# meltdown_interface.net
KiCad netlist of a schematic drawn in Altium Designer
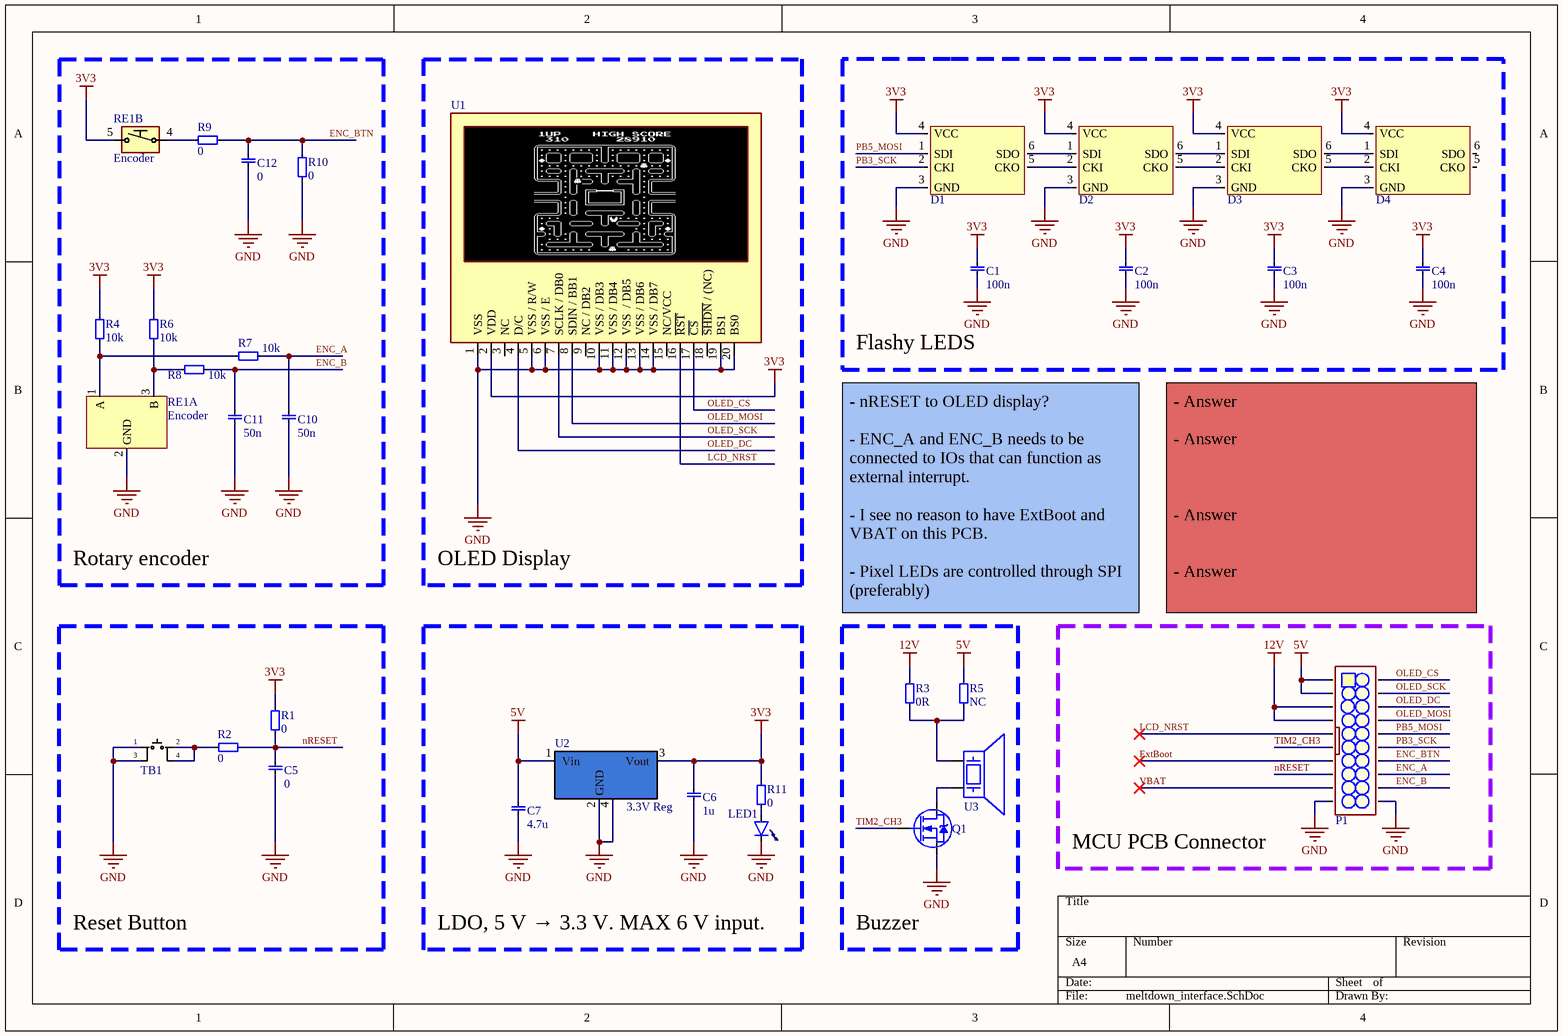
[diagram p0: meltdown_interface.SchDoc]

(export (version "E")
  (design (tool "Eeschema 10.0.6"))
  (components
    (comp (ref "C1")
      (value "100n")
      (footprint "0603 cap")
      (fields (field (name "Comment") "0603, capacitor"))
      (libsource (lib "jclib") (part "0603, capacitor"))
    )
    (comp (ref "C2")
      (value "100n")
      (footprint "0603 cap")
      (fields (field (name "Comment") "0603, capacitor"))
      (libsource (lib "jclib") (part "0603, capacitor"))
    )
    (comp (ref "C3")
      (value "100n")
      (footprint "0603 cap")
      (fields (field (name "Comment") "0603, capacitor"))
      (libsource (lib "jclib") (part "0603, capacitor"))
    )
    (comp (ref "C4")
      (value "100n")
      (footprint "0603 cap")
      (fields (field (name "Comment") "0603, capacitor"))
      (libsource (lib "jclib") (part "0603, capacitor"))
    )
    (comp (ref "C5")
      (value "0")
      (footprint "0603 cap")
      (fields (field (name "Comment") "0603, capacitor"))
      (libsource (lib "jclib") (part "0603, capacitor"))
    )
    (comp (ref "C6")
      (value "1u")
      (footprint "0603 cap")
      (fields (field (name "Comment") "0603, capacitor"))
      (libsource (lib "jclib") (part "0603, capacitor"))
    )
    (comp (ref "C7")
      (value "4.7u")
      (footprint "0603 cap")
      (fields (field (name "Comment") "0603, capacitor"))
      (libsource (lib "jclib") (part "0603, capacitor"))
    )
    (comp (ref "C10")
      (value "50n")
      (footprint "0603 cap")
      (fields (field (name "Comment") "0603, capacitor"))
      (libsource (lib "jclib") (part "0603, capacitor"))
    )
    (comp (ref "C11")
      (value "50n")
      (footprint "0603 cap")
      (fields (field (name "Comment") "0603, capacitor"))
      (libsource (lib "jclib") (part "0603, capacitor"))
    )
    (comp (ref "C12")
      (value "0")
      (footprint "0603 cap")
      (fields (field (name "Comment") "0603, capacitor"))
      (libsource (lib "jclib") (part "0603, capacitor"))
    )
    (comp (ref "D1")
      (value "Neo - SK9822")
      (footprint "SK9822")
      (libsource (lib "jclib") (part "Neo - SK9822"))
    )
    (comp (ref "D2")
      (value "Neo - SK9822")
      (footprint "SK9822")
      (libsource (lib "jclib") (part "Neo - SK9822"))
    )
    (comp (ref "D3")
      (value "Neo - SK9822")
      (footprint "SK9822")
      (libsource (lib "jclib") (part "Neo - SK9822"))
    )
    (comp (ref "D4")
      (value "Neo - SK9822")
      (footprint "SK9822")
      (libsource (lib "jclib") (part "Neo - SK9822"))
    )
    (comp (ref "LED1")
      (value "0805, LED")
      (footprint "0805_led")
      (libsource (lib "jclib") (part "0805, LED"))
    )
    (comp (ref "P1")
      (value "2x10 Ribbon Header")
      (footprint "2x10_RIBBON_CABLE_CON")
      (description "2.54 mm")
      (libsource (lib "jclib") (part "2x10 Ribbon Header"))
    )
    (comp (ref "Q1")
      (value "BSS138")
      (footprint "SOT323")
      (description "N-Channel Logic Level Enhancement Mode Field Effect Transistor")
      (libsource (lib "jclib") (part "BSS138"))
    )
    (comp (ref "R1")
      (value "0")
      (footprint "0603")
      (fields (field (name "Comment") "0603, resistor"))
      (libsource (lib "jclib") (part "0603, resistor"))
    )
    (comp (ref "R2")
      (value "0")
      (footprint "0603")
      (fields (field (name "Comment") "0603, resistor"))
      (libsource (lib "jclib") (part "0603, resistor"))
    )
    (comp (ref "R3")
      (value "0R")
      (footprint "0603")
      (fields (field (name "Comment") "0603, resistor"))
      (libsource (lib "jclib") (part "0603, resistor"))
    )
    (comp (ref "R4")
      (value "10k")
      (footprint "0603")
      (fields (field (name "Comment") "0603, resistor"))
      (libsource (lib "jclib") (part "0603, resistor"))
    )
    (comp (ref "R5")
      (value "NC")
      (footprint "0603")
      (fields (field (name "Comment") "0603, resistor"))
      (libsource (lib "jclib") (part "0603, resistor"))
    )
    (comp (ref "R6")
      (value "10k")
      (footprint "0603")
      (fields (field (name "Comment") "0603, resistor"))
      (libsource (lib "jclib") (part "0603, resistor"))
    )
    (comp (ref "R7")
      (value "10k")
      (footprint "0603")
      (fields (field (name "Comment") "0603, resistor"))
      (libsource (lib "jclib") (part "0603, resistor"))
    )
    (comp (ref "R8")
      (value "10k")
      (footprint "0603")
      (fields (field (name "Comment") "0603, resistor"))
      (libsource (lib "jclib") (part "0603, resistor"))
    )
    (comp (ref "R9")
      (value "0")
      (footprint "0603")
      (fields (field (name "Comment") "0603, resistor"))
      (libsource (lib "jclib") (part "0603, resistor"))
    )
    (comp (ref "R10")
      (value "0")
      (footprint "0603")
      (fields (field (name "Comment") "0603, resistor"))
      (libsource (lib "jclib") (part "0603, resistor"))
    )
    (comp (ref "R11")
      (value "0")
      (footprint "0603")
      (fields (field (name "Comment") "0603, resistor"))
      (libsource (lib "jclib") (part "0603, resistor"))
    )
    (comp (ref "RE1")
      (value "Encoder")
      (footprint "RotaryEncoder")
      (libsource (lib "") (part "Rotary Encoder with Button_1"))
    )
    (comp (ref "TB1")
      (value "Tactile Button")
      (footprint "tacButton smd")
      (description "Tactile Switch Small Low")
      (libsource (lib "jclib") (part "TacButton SMD"))
    )
    (comp (ref "U1")
      (value "NHD-2.7-12864WDW")
      (footprint "NHD-2.7-1286")
      (description "Graphic LCD Display Module White OLED - Passive Matrix Parallel/Serial 2.7\" (68.58mm) 128 x 64")
      (libsource (lib "jclib") (part "NHD-2.7-12864WDW"))
    )
    (comp (ref "U2")
      (value "3.3V Reg")
      (footprint "SOT223")
      (description "500 mA, Positive Fixed-Voltage, Low-Dropout Regulator")
      (libsource (lib "jclib") (part "MCP1826S"))
    )
    (comp (ref "U3")
      (value "Piezo element")
      (footprint "Piezo buzzer")
      (libsource (lib "jclib") (part "Piezo element"))
    )
  )
  (nets
    (net (code "1") (name "/ENC_A") (class "Default")
      (node (ref "C10") (pin "1") (pinfunction "1_1") (pintype "passive"))
      (node (ref "P1") (pin "13") (pinfunction "13_13") (pintype "passive"))
      (node (ref "R7") (pin "0") (pinfunction "0_0") (pintype "passive"))
    )
    (net (code "2") (name "/ENC_B") (class "Default")
      (node (ref "C11") (pin "1") (pinfunction "1_1") (pintype "passive"))
      (node (ref "P1") (pin "12") (pinfunction "12_12") (pintype "passive"))
      (node (ref "R8") (pin "0") (pinfunction "0_0") (pintype "passive"))
    )
    (net (code "3") (name "/ENC_BTN") (class "Default")
      (node (ref "C12") (pin "1") (pinfunction "1_1") (pintype "passive"))
      (node (ref "P1") (pin "14") (pinfunction "14_14") (pintype "passive"))
      (node (ref "R10") (pin "0") (pinfunction "0_0") (pintype "passive"))
      (node (ref "R9") (pin "1") (pinfunction "1_1") (pintype "passive"))
    )
    (net (code "4") (name "/ExtBoot") (class "Default")
      (node (ref "P1") (pin "7") (pinfunction "7_7") (pintype "passive+no_connect"))
    )
    (net (code "5") (name "/LCD_NRST") (class "Default")
      (node (ref "P1") (pin "5") (pinfunction "5_5") (pintype "passive"))
      (node (ref "U1") (pin "16") (pinfunction "~{RST}_16") (pintype "passive"))
    )
    (net (code "6") (name "/OLED_CS") (class "Default")
      (node (ref "P1") (pin "20") (pinfunction "20_20") (pintype "passive"))
      (node (ref "U1") (pin "17") (pinfunction "~{CS}_17") (pintype "passive"))
    )
    (net (code "7") (name "/OLED_DC") (class "Default")
      (node (ref "P1") (pin "18") (pinfunction "18_18") (pintype "passive"))
      (node (ref "U1") (pin "4") (pinfunction "D/C_4") (pintype "passive"))
    )
    (net (code "8") (name "/OLED_MOSI") (class "Default")
      (node (ref "P1") (pin "17") (pinfunction "17_17") (pintype "passive"))
      (node (ref "U1") (pin "8") (pinfunction "SDIN_/_BB1_8") (pintype "passive"))
    )
    (net (code "9") (name "/OLED_SCK") (class "Default")
      (node (ref "P1") (pin "19") (pinfunction "19_19") (pintype "passive"))
      (node (ref "U1") (pin "7") (pinfunction "SCLK_/_DB0_7") (pintype "passive"))
    )
    (net (code "10") (name "/PB3_SCK") (class "Default")
      (node (ref "D1") (pin "2") (pinfunction "CKI_2") (pintype "passive"))
      (node (ref "P1") (pin "15") (pinfunction "15_15") (pintype "passive"))
    )
    (net (code "11") (name "/PB5_MOSI") (class "Default")
      (node (ref "D1") (pin "1") (pinfunction "SDI_1") (pintype "passive"))
      (node (ref "P1") (pin "16") (pinfunction "16_16") (pintype "passive"))
    )
    (net (code "12") (name "/TIM2_CH3") (class "Default")
      (node (ref "P1") (pin "6") (pinfunction "6_6") (pintype "passive"))
      (node (ref "Q1") (pin "1") (pinfunction "G_1") (pintype "passive"))
    )
    (net (code "13") (name "/VBAT") (class "Default")
      (node (ref "P1") (pin "9") (pinfunction "9_9") (pintype "passive+no_connect"))
    )
    (net (code "14") (name "/nRESET") (class "Default")
      (node (ref "C5") (pin "1") (pinfunction "1_1") (pintype "passive"))
      (node (ref "P1") (pin "8") (pinfunction "8_8") (pintype "passive"))
      (node (ref "R1") (pin "0") (pinfunction "0_0") (pintype "passive"))
      (node (ref "R2") (pin "1") (pinfunction "1_1") (pintype "passive"))
    )
    (net (code "15") (name "3V3") (class "Default")
      (node (ref "C1") (pin "1") (pinfunction "1_1") (pintype "passive"))
      (node (ref "C2") (pin "1") (pinfunction "1_1") (pintype "passive"))
      (node (ref "C3") (pin "1") (pinfunction "1_1") (pintype "passive"))
      (node (ref "C4") (pin "1") (pinfunction "1_1") (pintype "passive"))
      (node (ref "C6") (pin "1") (pinfunction "1_1") (pintype "passive"))
      (node (ref "D1") (pin "4") (pinfunction "VCC_4") (pintype "passive"))
      (node (ref "D2") (pin "4") (pinfunction "VCC_4") (pintype "passive"))
      (node (ref "D3") (pin "4") (pinfunction "VCC_4") (pintype "passive"))
      (node (ref "D4") (pin "4") (pinfunction "VCC_4") (pintype "passive"))
      (node (ref "R1") (pin "1") (pinfunction "1_1") (pintype "passive"))
      (node (ref "R11") (pin "0") (pinfunction "0_0") (pintype "passive"))
      (node (ref "R4") (pin "0") (pinfunction "0_0") (pintype "passive"))
      (node (ref "R6") (pin "0") (pinfunction "0_0") (pintype "passive"))
      (node (ref "RE1") (pin "5") (pinfunction "B_5") (pintype "passive"))
      (node (ref "U1") (pin "2") (pinfunction "VDD_2") (pintype "passive"))
      (node (ref "U2") (pin "3") (pinfunction "Vout_3") (pintype "passive"))
    )
    (net (code "16") (name "5V") (class "Default")
      (node (ref "C7") (pin "1") (pinfunction "1_1") (pintype "passive"))
      (node (ref "P1") (pin "1") (pinfunction "1_1") (pintype "passive"))
      (node (ref "P1") (pin "2") (pinfunction "2_2") (pintype "passive"))
      (node (ref "R5") (pin "0") (pinfunction "0_0") (pintype "passive"))
      (node (ref "U2") (pin "1") (pinfunction "Vin_1") (pintype "passive"))
    )
    (net (code "17") (name "12V") (class "Default")
      (node (ref "P1") (pin "3") (pinfunction "3_3") (pintype "passive"))
      (node (ref "P1") (pin "4") (pinfunction "4_4") (pintype "passive"))
      (node (ref "R3") (pin "0") (pinfunction "0_0") (pintype "passive"))
    )
    (net (code "18") (name "GND") (class "Default")
      (node (ref "C1") (pin "0") (pinfunction "0_0") (pintype "passive"))
      (node (ref "C10") (pin "0") (pinfunction "0_0") (pintype "passive"))
      (node (ref "C11") (pin "0") (pinfunction "0_0") (pintype "passive"))
      (node (ref "C12") (pin "0") (pinfunction "0_0") (pintype "passive"))
      (node (ref "C2") (pin "0") (pinfunction "0_0") (pintype "passive"))
      (node (ref "C3") (pin "0") (pinfunction "0_0") (pintype "passive"))
      (node (ref "C4") (pin "0") (pinfunction "0_0") (pintype "passive"))
      (node (ref "C5") (pin "0") (pinfunction "0_0") (pintype "passive"))
      (node (ref "C6") (pin "0") (pinfunction "0_0") (pintype "passive"))
      (node (ref "C7") (pin "0") (pinfunction "0_0") (pintype "passive"))
      (node (ref "D1") (pin "3") (pinfunction "GND_3") (pintype "passive"))
      (node (ref "D2") (pin "3") (pinfunction "GND_3") (pintype "passive"))
      (node (ref "D3") (pin "3") (pinfunction "GND_3") (pintype "passive"))
      (node (ref "D4") (pin "3") (pinfunction "GND_3") (pintype "passive"))
      (node (ref "LED1") (pin "0") (pinfunction "Cathode_0") (pintype "passive"))
      (node (ref "P1") (pin "10") (pinfunction "10_10") (pintype "passive"))
      (node (ref "P1") (pin "11") (pinfunction "11_11") (pintype "passive"))
      (node (ref "Q1") (pin "3") (pinfunction "S_3") (pintype "passive"))
      (node (ref "R10") (pin "1") (pinfunction "1_1") (pintype "passive"))
      (node (ref "RE1") (pin "2") (pinfunction "GND_2") (pintype "passive"))
      (node (ref "TB1") (pin "1") (pinfunction "1_1") (pintype "passive"))
      (node (ref "TB1") (pin "3") (pinfunction "3_3") (pintype "passive"))
      (node (ref "U1") (pin "1") (pinfunction "VSS_1") (pintype "passive"))
      (node (ref "U1") (pin "10") (pinfunction "VSS_/_DB3_10") (pintype "passive"))
      (node (ref "U1") (pin "11") (pinfunction "VSS_/_DB4_11") (pintype "passive"))
      (node (ref "U1") (pin "12") (pinfunction "VSS__/_DB5_12") (pintype "passive"))
      (node (ref "U1") (pin "13") (pinfunction "VSS_/_DB6_13") (pintype "passive"))
      (node (ref "U1") (pin "14") (pinfunction "VSS_/_DB7_14") (pintype "passive"))
      (node (ref "U1") (pin "19") (pinfunction "BS1_19") (pintype "passive"))
      (node (ref "U1") (pin "20") (pinfunction "BS0_20") (pintype "passive"))
      (node (ref "U1") (pin "5") (pinfunction "VSS_/_R/W_5") (pintype "passive"))
      (node (ref "U1") (pin "6") (pinfunction "VSS_/_E_6") (pintype "passive"))
      (node (ref "U2") (pin "2") (pinfunction "GND_2") (pintype "passive"))
      (node (ref "U2") (pin "4") (pintype "passive"))
    )
    (net (code "19") (name "Net-(D1-CKO)") (class "Default")
      (node (ref "D1") (pin "5") (pinfunction "CKO_5") (pintype "passive"))
      (node (ref "D2") (pin "2") (pinfunction "CKI_2") (pintype "passive"))
    )
    (net (code "20") (name "Net-(D1-SDO)") (class "Default")
      (node (ref "D1") (pin "6") (pinfunction "SDO_6") (pintype "passive"))
      (node (ref "D2") (pin "1") (pinfunction "SDI_1") (pintype "passive"))
    )
    (net (code "21") (name "Net-(D2-CKO)") (class "Default")
      (node (ref "D2") (pin "5") (pinfunction "CKO_5") (pintype "passive"))
      (node (ref "D3") (pin "2") (pinfunction "CKI_2") (pintype "passive"))
    )
    (net (code "22") (name "Net-(D2-SDO)") (class "Default")
      (node (ref "D2") (pin "6") (pinfunction "SDO_6") (pintype "passive"))
      (node (ref "D3") (pin "1") (pinfunction "SDI_1") (pintype "passive"))
    )
    (net (code "23") (name "Net-(D3-CKO)") (class "Default")
      (node (ref "D3") (pin "5") (pinfunction "CKO_5") (pintype "passive"))
      (node (ref "D4") (pin "2") (pinfunction "CKI_2") (pintype "passive"))
    )
    (net (code "24") (name "Net-(D3-SDO)") (class "Default")
      (node (ref "D3") (pin "6") (pinfunction "SDO_6") (pintype "passive"))
      (node (ref "D4") (pin "1") (pinfunction "SDI_1") (pintype "passive"))
    )
    (net (code "25") (name "Net-(LED1-Pad1)") (class "Default")
      (node (ref "LED1") (pin "1") (pinfunction "1_1") (pintype "passive"))
      (node (ref "R11") (pin "1") (pinfunction "1_1") (pintype "passive"))
    )
    (net (code "26") (name "Net-(Q1-D)") (class "Default")
      (node (ref "Q1") (pin "2") (pinfunction "D_2") (pintype "passive"))
      (node (ref "U3") (pin "2") (pinfunction "2_2") (pintype "passive"))
    )
    (net (code "27") (name "Net-(R2-Pad0)") (class "Default")
      (node (ref "R2") (pin "0") (pinfunction "0_0") (pintype "passive"))
      (node (ref "TB1") (pin "2") (pinfunction "2_2") (pintype "passive"))
      (node (ref "TB1") (pin "4") (pinfunction "4_4") (pintype "passive"))
    )
    (net (code "28") (name "Net-(R3-Pad1)") (class "Default")
      (node (ref "R3") (pin "1") (pinfunction "1_1") (pintype "passive"))
      (node (ref "R5") (pin "1") (pinfunction "1_1") (pintype "passive"))
      (node (ref "U3") (pin "1") (pinfunction "1_1") (pintype "passive"))
    )
    (net (code "29") (name "Net-(R9-Pad0)") (class "Default")
      (node (ref "R9") (pin "0") (pinfunction "0_0") (pintype "passive"))
      (node (ref "RE1") (pin "4") (pinfunction "B_4") (pintype "passive"))
    )
    (net (code "30") (name "Net-(RE1A-A)") (class "Default")
      (node (ref "R4") (pin "1") (pinfunction "1_1") (pintype "passive"))
      (node (ref "R7") (pin "1") (pinfunction "1_1") (pintype "passive"))
      (node (ref "RE1") (pin "1") (pinfunction "A_1") (pintype "passive"))
    )
    (net (code "31") (name "Net-(RE1A-B)") (class "Default")
      (node (ref "R6") (pin "1") (pinfunction "1_1") (pintype "passive"))
      (node (ref "R8") (pin "1") (pinfunction "1_1") (pintype "passive"))
      (node (ref "RE1") (pin "3") (pinfunction "B_3") (pintype "passive"))
    )
    (net (code "32") (name "unconnected-(D4-CKO-Pad5)") (class "Default")
      (node (ref "D4") (pin "5") (pinfunction "CKO_5") (pintype "passive"))
    )
    (net (code "33") (name "unconnected-(D4-SDO-Pad6)") (class "Default")
      (node (ref "D4") (pin "6") (pinfunction "SDO_6") (pintype "passive"))
    )
    (net (code "34") (name "unconnected-(U1-NC-Pad3)") (class "Default")
      (node (ref "U1") (pin "3") (pinfunction "NC_3") (pintype "passive"))
    )
    (net (code "35") (name "unconnected-(U1-NC_{slash}_DB2-Pad9)") (class "Default")
      (node (ref "U1") (pin "9") (pinfunction "NC_/_DB2_9") (pintype "passive"))
    )
    (net (code "36") (name "unconnected-(U1-NC{slash}VCC-Pad15)") (class "Default")
      (node (ref "U1") (pin "15") (pinfunction "NC/VCC_15") (pintype "passive"))
    )
    (net (code "37") (name "unconnected-(U1-~{SHDN}_{slash}_(NC)-Pad18)") (class "Default")
      (node (ref "U1") (pin "18") (pinfunction "~{SHDN}_/_(NC)_18") (pintype "passive"))
    )
  )
)
